# STM-main.net
KiCad netlist of a schematic drawn in Altium Designer
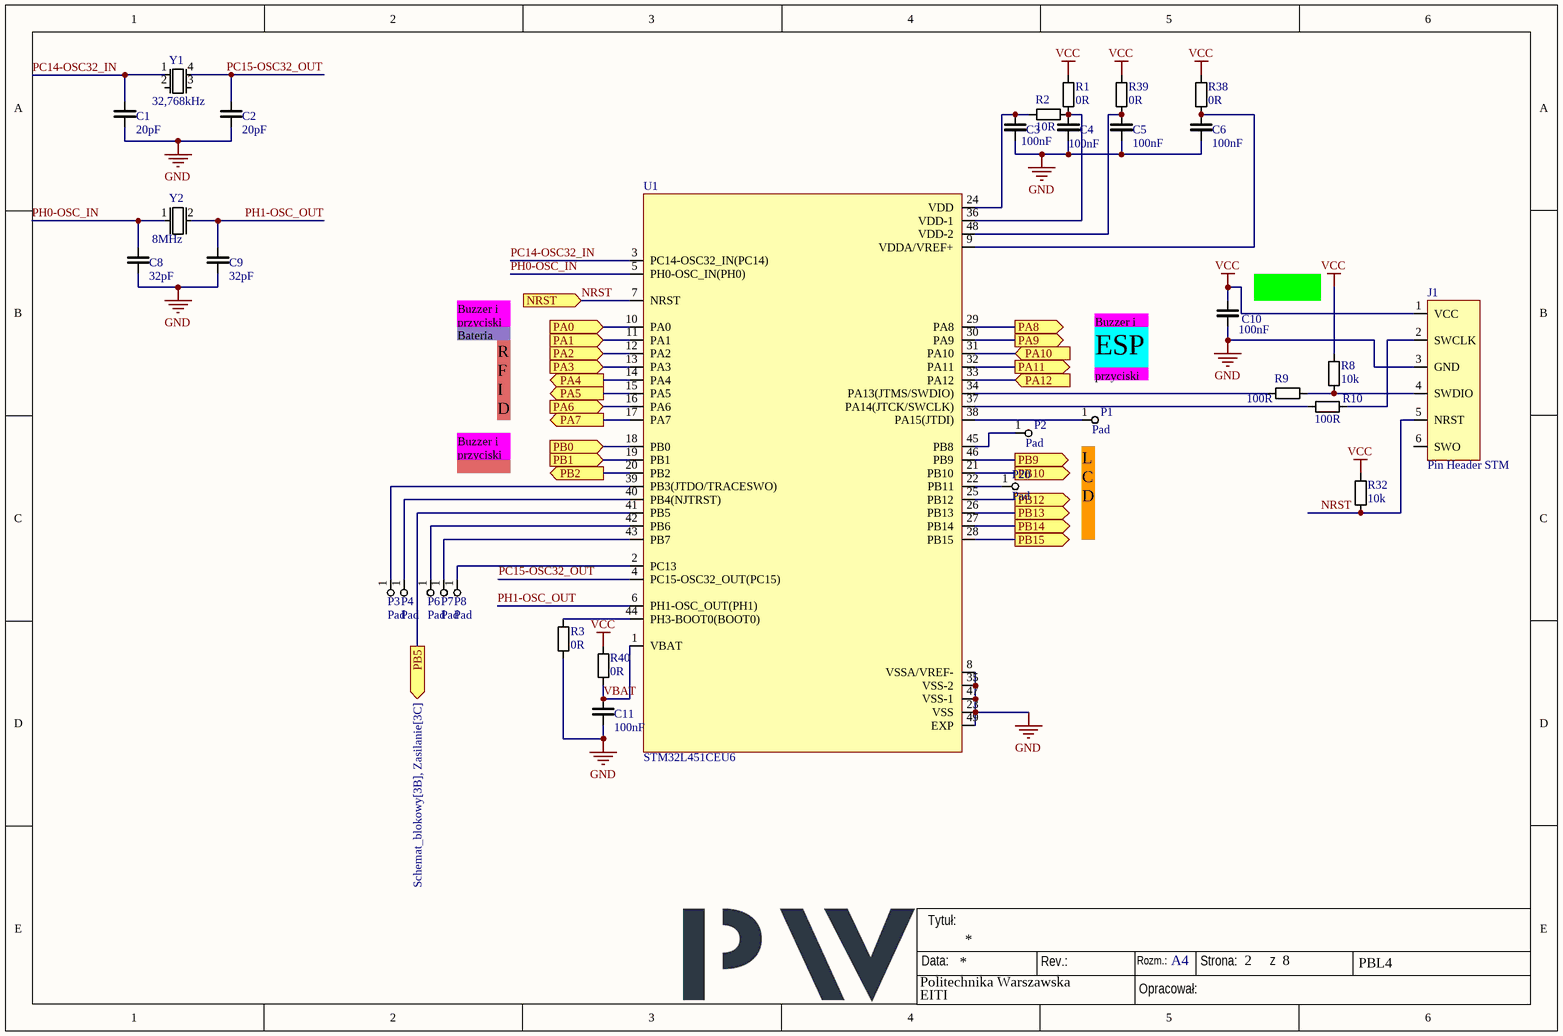
[diagram p0: STM-main.SchDoc]

(export (version "E")
  (design (tool "Eeschema 10.0.6"))
  (components
    (comp (ref "C1")
      (value "20pF")
      (footprint "0603_CAP")
      (description "Ceramic capacitor")
      (libsource (lib "Cap") (part "Cap"))
    )
    (comp (ref "C2")
      (value "20pF")
      (footprint "0603_CAP")
      (description "Ceramic capacitor")
      (libsource (lib "Cap") (part "Cap"))
    )
    (comp (ref "C3")
      (value "100nF")
      (footprint "0603_CAP")
      (description "Ceramic capacitor")
      (libsource (lib "Cap") (part "Cap"))
    )
    (comp (ref "C4")
      (value "100nF")
      (footprint "0603_CAP")
      (description "Ceramic capacitor")
      (libsource (lib "Cap") (part "Cap"))
    )
    (comp (ref "C5")
      (value "100nF")
      (footprint "0603_CAP")
      (description "Ceramic capacitor")
      (libsource (lib "Cap") (part "Cap"))
    )
    (comp (ref "C6")
      (value "100nF")
      (footprint "0603_CAP")
      (description "Ceramic capacitor")
      (libsource (lib "Cap") (part "Cap"))
    )
    (comp (ref "C8")
      (value "32pF")
      (footprint "0603_CAP")
      (description "Ceramic capacitor")
      (libsource (lib "Cap") (part "Cap"))
    )
    (comp (ref "C9")
      (value "32pF")
      (footprint "0603_CAP")
      (description "Ceramic capacitor")
      (libsource (lib "Cap") (part "Cap"))
    )
    (comp (ref "C10")
      (value "100nF")
      (footprint "0603_CAP")
      (description "Ceramic capacitor")
      (libsource (lib "Cap") (part "Cap"))
    )
    (comp (ref "C11")
      (value "100nF")
      (footprint "0603_CAP")
      (description "Ceramic capacitor")
      (libsource (lib "Cap") (part "Cap"))
    )
    (comp (ref "J1")
      (value "Pin Header STM")
      (footprint "SAMTEC_TSW-112-16-T-S-06")
      (libsource (lib "STM") (part "Pin Header STM"))
    )
    (comp (ref "P1") (value "Pad") (footprint "pad") (libsource (lib "PinLutowniczy") (part "Pad")))
    (comp (ref "P2") (value "Pad") (footprint "pad") (libsource (lib "PinLutowniczy") (part "Pad")))
    (comp (ref "P3") (value "Pad") (footprint "pad") (libsource (lib "PinLutowniczy") (part "Pad")))
    (comp (ref "P4") (value "Pad") (footprint "pad") (libsource (lib "PinLutowniczy") (part "Pad")))
    (comp (ref "P6") (value "Pad") (footprint "pad") (libsource (lib "PinLutowniczy") (part "Pad")))
    (comp (ref "P7") (value "Pad") (footprint "pad") (libsource (lib "PinLutowniczy") (part "Pad")))
    (comp (ref "P8") (value "Pad") (footprint "pad") (libsource (lib "PinLutowniczy") (part "Pad")))
    (comp (ref "P20") (value "Pad") (footprint "pad") (libsource (lib "PinLutowniczy") (part "Pad")))
    (comp (ref "R1")
      (value "0R")
      (footprint "0603_RES")
      (description "Resistor")
      (libsource (lib "RES") (part "RES"))
    )
    (comp (ref "R2")
      (value "10R")
      (footprint "0603_RES")
      (description "Resistor")
      (libsource (lib "RES") (part "RES"))
    )
    (comp (ref "R3")
      (value "0R")
      (footprint "0603_RES")
      (description "Resistor")
      (libsource (lib "RES") (part "RES"))
    )
    (comp (ref "R8")
      (value "10k")
      (footprint "0603_RES")
      (description "Resistor")
      (libsource (lib "RES") (part "RES"))
    )
    (comp (ref "R9")
      (value "100R")
      (footprint "0603_RES")
      (description "Resistor")
      (libsource (lib "RES") (part "RES"))
    )
    (comp (ref "R10")
      (value "100R")
      (footprint "0603_RES")
      (description "Resistor")
      (libsource (lib "RES") (part "RES"))
    )
    (comp (ref "R32")
      (value "10k")
      (footprint "0603_RES")
      (description "Resistor")
      (libsource (lib "RES") (part "RES"))
    )
    (comp (ref "R38")
      (value "0R")
      (footprint "0603_RES")
      (description "Resistor")
      (libsource (lib "RES") (part "RES"))
    )
    (comp (ref "R39")
      (value "0R")
      (footprint "0603_RES")
      (description "Resistor")
      (libsource (lib "RES") (part "RES"))
    )
    (comp (ref "R40")
      (value "0R")
      (footprint "0603_RES")
      (description "Resistor")
      (libsource (lib "RES") (part "RES"))
    )
    (comp (ref "U1")
      (value "STM32L451CEU6")
      (footprint "QFN50P700X700X60-49N")
      (libsource (lib "STM") (part "STM32L451CEU6"))
    )
    (comp (ref "Y1")
      (value "32,768kHz")
      (footprint "Q 0,032768-SMQ32SL-12,5-20-T1-LF")
      (description "Oscilator")
      (fields (field (name "PARTNUMBER") "Q 0,032768-SMQ32SL-12,5-20-T1-LF"))
      (libsource (lib "Oscylator") (part "Oscylator4"))
    )
    (comp (ref "Y2")
      (value "8MHz")
      (footprint "ATS080BSM-1E")
      (description "Oscilator")
      (fields (field (name "PARTNUMBER") "ATS080BSM-1E"))
      (libsource (lib "Oscylator") (part "Oscylator"))
    )
  )
  (nets
    (net (code "1") (name "/NRST") (class "Default")
      (node (ref "J1") (pin "5") (pinfunction "NRST_5") (pintype "passive"))
      (node (ref "R32") (pin "1") (pinfunction "1_1") (pintype "passive"))
      (node (ref "U1") (pin "7") (pinfunction "NRST_7") (pintype "passive"))
    )
    (net (code "2") (name "/PA0") (class "Default")
      (node (ref "U1") (pin "10") (pinfunction "PA0_10") (pintype "passive"))
    )
    (net (code "3") (name "/PA1") (class "Default")
      (node (ref "U1") (pin "11") (pinfunction "PA1_11") (pintype "passive"))
    )
    (net (code "4") (name "/PA2") (class "Default")
      (node (ref "U1") (pin "12") (pinfunction "PA2_12") (pintype "passive"))
    )
    (net (code "5") (name "/PA3") (class "Default")
      (node (ref "U1") (pin "13") (pinfunction "PA3_13") (pintype "passive"))
    )
    (net (code "6") (name "/PA4") (class "Default")
      (node (ref "U1") (pin "14") (pinfunction "PA4_14") (pintype "passive"))
    )
    (net (code "7") (name "/PA5") (class "Default")
      (node (ref "U1") (pin "15") (pinfunction "PA5_15") (pintype "passive"))
    )
    (net (code "8") (name "/PA6") (class "Default")
      (node (ref "U1") (pin "16") (pinfunction "PA6_16") (pintype "passive"))
    )
    (net (code "9") (name "/PA7") (class "Default")
      (node (ref "U1") (pin "17") (pinfunction "PA7_17") (pintype "passive"))
    )
    (net (code "10") (name "/PA8") (class "Default")
      (node (ref "U1") (pin "29") (pinfunction "PA8_29") (pintype "passive"))
    )
    (net (code "11") (name "/PA9") (class "Default")
      (node (ref "U1") (pin "30") (pinfunction "PA9_30") (pintype "passive"))
    )
    (net (code "12") (name "/PA10") (class "Default")
      (node (ref "U1") (pin "31") (pinfunction "PA10_31") (pintype "passive"))
    )
    (net (code "13") (name "/PA11") (class "Default")
      (node (ref "U1") (pin "32") (pinfunction "PA11_32") (pintype "passive"))
    )
    (net (code "14") (name "/PA12") (class "Default")
      (node (ref "U1") (pin "33") (pinfunction "PA12_33") (pintype "passive"))
    )
    (net (code "15") (name "/PB0") (class "Default")
      (node (ref "U1") (pin "18") (pinfunction "PB0_18") (pintype "passive"))
    )
    (net (code "16") (name "/PB1") (class "Default")
      (node (ref "U1") (pin "19") (pinfunction "PB1_19") (pintype "passive"))
    )
    (net (code "17") (name "/PB2") (class "Default")
      (node (ref "U1") (pin "20") (pinfunction "PB2_20") (pintype "passive"))
    )
    (net (code "18") (name "/PB5") (class "Default")
      (node (ref "U1") (pin "41") (pinfunction "PB5_41") (pintype "passive"))
    )
    (net (code "19") (name "/PB9") (class "Default")
      (node (ref "U1") (pin "46") (pinfunction "PB9_46") (pintype "passive"))
    )
    (net (code "20") (name "/PB10") (class "Default")
      (node (ref "U1") (pin "21") (pinfunction "PB10_21") (pintype "passive"))
    )
    (net (code "21") (name "/PB12") (class "Default")
      (node (ref "U1") (pin "25") (pinfunction "PB12_25") (pintype "passive"))
    )
    (net (code "22") (name "/PB13") (class "Default")
      (node (ref "U1") (pin "26") (pinfunction "PB13_26") (pintype "passive"))
    )
    (net (code "23") (name "/PB14") (class "Default")
      (node (ref "U1") (pin "27") (pinfunction "PB14_27") (pintype "passive"))
    )
    (net (code "24") (name "/PB15") (class "Default")
      (node (ref "U1") (pin "28") (pinfunction "PB15_28") (pintype "passive"))
    )
    (net (code "25") (name "/PC14-OSC32_IN") (class "Default")
      (node (ref "C1") (pin "2") (pinfunction "2_2") (pintype "passive"))
      (node (ref "U1") (pin "3") (pinfunction "PC14-OSC32_IN(PC14)_3") (pintype "passive"))
      (node (ref "Y1") (pin "1") (pintype "passive"))
    )
    (net (code "26") (name "/PC15-OSC32_OUT") (class "Default")
      (node (ref "C2") (pin "2") (pinfunction "2_2") (pintype "passive"))
      (node (ref "U1") (pin "4") (pinfunction "PC15-OSC32_OUT(PC15)_4") (pintype "passive"))
      (node (ref "Y1") (pin "4") (pintype "passive"))
    )
    (net (code "27") (name "/PH0-OSC_IN") (class "Default")
      (node (ref "C8") (pin "2") (pinfunction "2_2") (pintype "passive"))
      (node (ref "U1") (pin "5") (pinfunction "PH0-OSC_IN(PH0)_5") (pintype "passive"))
      (node (ref "Y2") (pin "1") (pintype "passive"))
    )
    (net (code "28") (name "/PH1-OSC_OUT") (class "Default")
      (node (ref "C9") (pin "2") (pinfunction "2_2") (pintype "passive"))
      (node (ref "U1") (pin "6") (pinfunction "PH1-OSC_OUT(PH1)_6") (pintype "passive"))
      (node (ref "Y2") (pin "2") (pintype "passive"))
    )
    (net (code "29") (name "/VBAT") (class "Default")
      (node (ref "C11") (pin "2") (pinfunction "2_2") (pintype "passive"))
      (node (ref "R40") (pin "1") (pinfunction "1_1") (pintype "passive"))
      (node (ref "U1") (pin "1") (pinfunction "VBAT_1") (pintype "passive"))
    )
    (net (code "30") (name "GND") (class "Default")
      (node (ref "C1") (pin "1") (pinfunction "1_1") (pintype "passive"))
      (node (ref "C10") (pin "1") (pinfunction "1_1") (pintype "passive"))
      (node (ref "C11") (pin "1") (pinfunction "1_1") (pintype "passive"))
      (node (ref "C2") (pin "1") (pinfunction "1_1") (pintype "passive"))
      (node (ref "C3") (pin "1") (pinfunction "1_1") (pintype "passive"))
      (node (ref "C4") (pin "1") (pinfunction "1_1") (pintype "passive"))
      (node (ref "C5") (pin "1") (pinfunction "1_1") (pintype "passive"))
      (node (ref "C6") (pin "1") (pinfunction "1_1") (pintype "passive"))
      (node (ref "C8") (pin "1") (pinfunction "1_1") (pintype "passive"))
      (node (ref "C9") (pin "1") (pinfunction "1_1") (pintype "passive"))
      (node (ref "J1") (pin "3") (pinfunction "GND_3") (pintype "passive"))
      (node (ref "R3") (pin "1") (pinfunction "1_1") (pintype "passive"))
      (node (ref "U1") (pin "23") (pinfunction "VSS_23") (pintype "passive"))
      (node (ref "U1") (pin "35") (pinfunction "VSS-2_35") (pintype "passive"))
      (node (ref "U1") (pin "47") (pinfunction "VSS-1_47") (pintype "passive"))
      (node (ref "U1") (pin "49") (pinfunction "EXP_49") (pintype "passive"))
      (node (ref "U1") (pin "8") (pinfunction "VSSA/VREF-_8") (pintype "passive"))
    )
    (net (code "31") (name "Net-(J1-SWCLK)") (class "Default")
      (node (ref "J1") (pin "2") (pinfunction "SWCLK_2") (pintype "passive"))
      (node (ref "R10") (pin "2") (pinfunction "2_2") (pintype "passive"))
    )
    (net (code "32") (name "Net-(J1-SWDIO)") (class "Default")
      (node (ref "J1") (pin "4") (pinfunction "SWDIO_4") (pintype "passive"))
      (node (ref "R8") (pin "1") (pinfunction "1_1") (pintype "passive"))
      (node (ref "R9") (pin "2") (pinfunction "2_2") (pintype "passive"))
    )
    (net (code "33") (name "Net-(U1-PA13(JTMS{slash}SWDIO))") (class "Default")
      (node (ref "R9") (pin "1") (pinfunction "1_1") (pintype "passive"))
      (node (ref "U1") (pin "34") (pinfunction "PA13(JTMS/SWDIO)_34") (pintype "passive"))
    )
    (net (code "34") (name "Net-(U1-PA14(JTCK{slash}SWCLK))") (class "Default")
      (node (ref "R10") (pin "1") (pinfunction "1_1") (pintype "passive"))
      (node (ref "U1") (pin "37") (pinfunction "PA14(JTCK/SWCLK)_37") (pintype "passive"))
    )
    (net (code "35") (name "Net-(U1-PA15(JTDI))") (class "Default")
      (node (ref "P1") (pin "1") (pintype "passive"))
      (node (ref "U1") (pin "38") (pinfunction "PA15(JTDI)_38") (pintype "passive"))
    )
    (net (code "36") (name "Net-(U1-PB3(JTDO{slash}TRACESWO))") (class "Default")
      (node (ref "P3") (pin "1") (pintype "passive"))
      (node (ref "U1") (pin "39") (pinfunction "PB3(JTDO/TRACESWO)_39") (pintype "passive"))
    )
    (net (code "37") (name "Net-(U1-PB4(NJTRST))") (class "Default")
      (node (ref "P4") (pin "1") (pintype "passive"))
      (node (ref "U1") (pin "40") (pinfunction "PB4(NJTRST)_40") (pintype "passive"))
    )
    (net (code "38") (name "Net-(U1-PB6)") (class "Default")
      (node (ref "P6") (pin "1") (pintype "passive"))
      (node (ref "U1") (pin "42") (pinfunction "PB6_42") (pintype "passive"))
    )
    (net (code "39") (name "Net-(U1-PB7)") (class "Default")
      (node (ref "P7") (pin "1") (pintype "passive"))
      (node (ref "U1") (pin "43") (pinfunction "PB7_43") (pintype "passive"))
    )
    (net (code "40") (name "Net-(U1-PB8)") (class "Default")
      (node (ref "P2") (pin "1") (pintype "passive"))
      (node (ref "U1") (pin "45") (pinfunction "PB8_45") (pintype "passive"))
    )
    (net (code "41") (name "Net-(U1-PB11)") (class "Default")
      (node (ref "P20") (pin "1") (pintype "passive"))
      (node (ref "U1") (pin "22") (pinfunction "PB11_22") (pintype "passive"))
    )
    (net (code "42") (name "Net-(U1-PC13)") (class "Default")
      (node (ref "P8") (pin "1") (pintype "passive"))
      (node (ref "U1") (pin "2") (pinfunction "PC13_2") (pintype "passive"))
    )
    (net (code "43") (name "Net-(U1-PH3-BOOT0(BOOT0))") (class "Default")
      (node (ref "R3") (pin "2") (pinfunction "2_2") (pintype "passive"))
      (node (ref "U1") (pin "44") (pinfunction "PH3-BOOT0(BOOT0)_44") (pintype "passive"))
    )
    (net (code "44") (name "Net-(U1-VDD)") (class "Default")
      (node (ref "C3") (pin "2") (pinfunction "2_2") (pintype "passive"))
      (node (ref "R2") (pin "1") (pinfunction "1_1") (pintype "passive"))
      (node (ref "U1") (pin "24") (pinfunction "VDD_24") (pintype "passive"))
    )
    (net (code "45") (name "Net-(U1-VDD-1)") (class "Default")
      (node (ref "C4") (pin "2") (pinfunction "2_2") (pintype "passive"))
      (node (ref "R1") (pin "1") (pinfunction "1_1") (pintype "passive"))
      (node (ref "R2") (pin "2") (pinfunction "2_2") (pintype "passive"))
      (node (ref "U1") (pin "36") (pinfunction "VDD-1_36") (pintype "passive"))
    )
    (net (code "46") (name "Net-(U1-VDD-2)") (class "Default")
      (node (ref "C5") (pin "2") (pinfunction "2_2") (pintype "passive"))
      (node (ref "R39") (pin "1") (pinfunction "1_1") (pintype "passive"))
      (node (ref "U1") (pin "48") (pinfunction "VDD-2_48") (pintype "passive"))
    )
    (net (code "47") (name "Net-(U1-VDDA{slash}VREF+)") (class "Default")
      (node (ref "C6") (pin "2") (pinfunction "2_2") (pintype "passive"))
      (node (ref "R38") (pin "1") (pinfunction "1_1") (pintype "passive"))
      (node (ref "U1") (pin "9") (pinfunction "VDDA/VREF+_9") (pintype "passive"))
    )
    (net (code "48") (name "VCC") (class "Default")
      (node (ref "C10") (pin "2") (pinfunction "2_2") (pintype "passive"))
      (node (ref "J1") (pin "1") (pinfunction "VCC_1") (pintype "passive"))
      (node (ref "R1") (pin "2") (pinfunction "2_2") (pintype "passive"))
      (node (ref "R32") (pin "2") (pinfunction "2_2") (pintype "passive"))
      (node (ref "R38") (pin "2") (pinfunction "2_2") (pintype "passive"))
      (node (ref "R39") (pin "2") (pinfunction "2_2") (pintype "passive"))
      (node (ref "R40") (pin "2") (pinfunction "2_2") (pintype "passive"))
      (node (ref "R8") (pin "2") (pinfunction "2_2") (pintype "passive"))
    )
    (net (code "49") (name "unconnected-(J1-SWO-Pad6)") (class "Default")
      (node (ref "J1") (pin "6") (pinfunction "SWO_6") (pintype "passive"))
    )
    (net (code "50") (name "unconnected-(Y1-Pad2)") (class "Default")
      (node (ref "Y1") (pin "2") (pintype "passive"))
    )
    (net (code "51") (name "unconnected-(Y1-Pad3)") (class "Default")
      (node (ref "Y1") (pin "3") (pintype "passive"))
    )
  )
)
